# MetalDetector.net
KiCad netlist of a schematic drawn in EAGLE
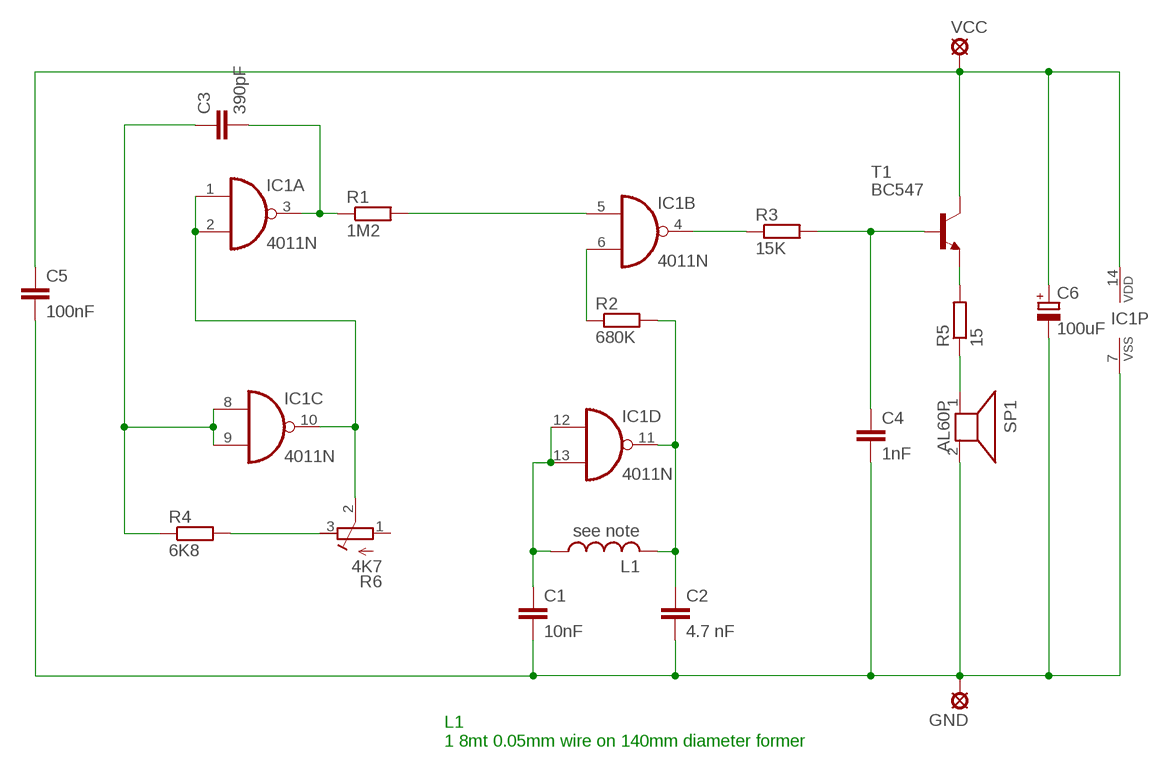
[diagram p0: schematic, sheet 1]

(export (version "E")
  (design (tool "Eeschema 10.0.6"))
  (components
    (comp (ref "C1")
      (value "10nF")
      (footprint "eagle-import:C025-025X050")
      (libsource (lib "eagle-import") (part "C-EU025-025X050"))
    )
    (comp (ref "C2")
      (value "4.7 nF")
      (footprint "eagle-import:C025-025X050")
      (libsource (lib "eagle-import") (part "C-EU025-025X050"))
    )
    (comp (ref "C3")
      (value "390pF")
      (footprint "eagle-import:C025-025X050")
      (libsource (lib "eagle-import") (part "C-EU025-025X050"))
    )
    (comp (ref "C4")
      (value "1nF")
      (footprint "eagle-import:C025-025X050")
      (libsource (lib "eagle-import") (part "C-EU025-025X050"))
    )
    (comp (ref "C5")
      (value "100nF")
      (footprint "eagle-import:C025-025X050")
      (libsource (lib "eagle-import") (part "C-EU025-025X050"))
    )
    (comp (ref "C6")
      (value "100uF")
      (footprint "eagle-import:E5-8,5")
      (libsource (lib "eagle-import") (part "CPOL-EUE5-8.5"))
    )
    (comp (ref "GND")
      (value "LSP10")
      (footprint "eagle-import:LSP10")
      (libsource (lib "eagle-import") (part "LSP10"))
    )
    (comp (ref "IC1")
      (value "4011N")
      (footprint "eagle-import:DIL14")
      (libsource (lib "eagle-import") (part "4011N"))
    )
    (comp (ref "L1")
      (value "see note")
      (footprint "eagle-import:6000-XXXX-RC")
      (libsource (lib "eagle-import") (part "L-US6000-XXX-RC"))
    )
    (comp (ref "R1")
      (value "1M2")
      (footprint "eagle-import:0207_12")
      (libsource (lib "eagle-import") (part "R-EU_0207/12"))
    )
    (comp (ref "R2")
      (value "680K")
      (footprint "eagle-import:0207_12")
      (libsource (lib "eagle-import") (part "R-EU_0207/12"))
    )
    (comp (ref "R3")
      (value "15K")
      (footprint "eagle-import:0207_12")
      (libsource (lib "eagle-import") (part "R-EU_0207/12"))
    )
    (comp (ref "R4")
      (value "6K8")
      (footprint "eagle-import:0207_12")
      (libsource (lib "eagle-import") (part "R-EU_0207/12"))
    )
    (comp (ref "R5")
      (value "15")
      (footprint "eagle-import:0207_12")
      (libsource (lib "eagle-import") (part "R-EU_0207/12"))
    )
    (comp (ref "R6")
      (value "4K7")
      (footprint "eagle-import:RTRIM3339P")
      (libsource (lib "eagle-import") (part "R-TRIMM3339P"))
    )
    (comp (ref "SP1")
      (value "AL60P")
      (footprint "eagle-import:AL60P")
      (libsource (lib "eagle-import") (part "AL60P"))
    )
    (comp (ref "T1")
      (value "BC547")
      (footprint "eagle-import:TO92")
      (libsource (lib "eagle-import") (part "BC547"))
    )
    (comp (ref "VCC")
      (value "LSP10")
      (footprint "eagle-import:LSP10")
      (libsource (lib "eagle-import") (part "LSP10"))
    )
  )
  (nets
    (net (code "1") (name "Net-(IC1A-I0)") (class "Default")
      (node (ref "IC1") (pin "1") (pinfunction "I0_1") (pintype "input"))
      (node (ref "IC1") (pin "10") (pinfunction "O_10") (pintype "output"))
      (node (ref "IC1") (pin "2") (pinfunction "I1_2") (pintype "input"))
      (node (ref "R6") (pin "2") (pinfunction "S_2") (pintype "passive"))
    )
    (net (code "2") (name "Net-(IC1A-O)") (class "Default")
      (node (ref "C3") (pin "2") (pinfunction "2_2") (pintype "passive"))
      (node (ref "IC1") (pin "3") (pinfunction "O_3") (pintype "output"))
      (node (ref "R1") (pin "1") (pinfunction "1_1") (pintype "passive"))
    )
    (net (code "3") (name "Net-(IC1B-I0)") (class "Default")
      (node (ref "IC1") (pin "5") (pinfunction "I0_5") (pintype "input"))
      (node (ref "R1") (pin "2") (pinfunction "2_2") (pintype "passive"))
    )
    (net (code "4") (name "Net-(IC1B-I1)") (class "Default")
      (node (ref "IC1") (pin "6") (pinfunction "I1_6") (pintype "input"))
      (node (ref "R2") (pin "1") (pinfunction "1_1") (pintype "passive"))
    )
    (net (code "5") (name "Net-(IC1B-O)") (class "Default")
      (node (ref "IC1") (pin "4") (pinfunction "O_4") (pintype "output"))
      (node (ref "R3") (pin "1") (pinfunction "1_1") (pintype "passive"))
    )
    (net (code "6") (name "Net-(IC1C-I0)") (class "Default")
      (node (ref "C3") (pin "1") (pinfunction "1_1") (pintype "passive"))
      (node (ref "IC1") (pin "8") (pinfunction "I0_8") (pintype "input"))
      (node (ref "IC1") (pin "9") (pinfunction "I1_9") (pintype "input"))
      (node (ref "R4") (pin "1") (pinfunction "1_1") (pintype "passive"))
    )
    (net (code "7") (name "Net-(IC1D-I0)") (class "Default")
      (node (ref "C1") (pin "1") (pinfunction "1_1") (pintype "passive"))
      (node (ref "IC1") (pin "12") (pinfunction "I0_12") (pintype "input"))
      (node (ref "IC1") (pin "13") (pinfunction "I1_13") (pintype "input"))
      (node (ref "L1") (pin "1") (pinfunction "1_1") (pintype "passive"))
    )
    (net (code "8") (name "Net-(IC1D-O)") (class "Default")
      (node (ref "C2") (pin "1") (pinfunction "1_1") (pintype "passive"))
      (node (ref "IC1") (pin "11") (pinfunction "O_11") (pintype "output"))
      (node (ref "L1") (pin "2") (pinfunction "2_2") (pintype "passive"))
      (node (ref "R2") (pin "2") (pinfunction "2_2") (pintype "passive"))
    )
    (net (code "9") (name "Net-(IC1E-VDD)") (class "Default")
      (node (ref "C5") (pin "1") (pinfunction "1_1") (pintype "passive"))
      (node (ref "C6") (pin "+") (pinfunction "+_+") (pintype "passive"))
      (node (ref "IC1") (pin "14") (pinfunction "VDD_14") (pintype "power_in"))
      (node (ref "T1") (pin "3") (pinfunction "C_3") (pintype "passive"))
      (node (ref "VCC") (pin "MP") (pinfunction "MP_MP") (pintype "passive"))
    )
    (net (code "10") (name "Net-(IC1E-VSS)") (class "Default")
      (node (ref "C1") (pin "2") (pinfunction "2_2") (pintype "passive"))
      (node (ref "C2") (pin "2") (pinfunction "2_2") (pintype "passive"))
      (node (ref "C4") (pin "2") (pinfunction "2_2") (pintype "passive"))
      (node (ref "C5") (pin "2") (pinfunction "2_2") (pintype "passive"))
      (node (ref "C6") (pin "-") (pinfunction "-_-") (pintype "passive"))
      (node (ref "GND") (pin "MP") (pinfunction "MP_MP") (pintype "passive"))
      (node (ref "IC1") (pin "7") (pinfunction "VSS_7") (pintype "power_in"))
      (node (ref "SP1") (pin "2") (pinfunction "2_2") (pintype "passive"))
    )
    (net (code "11") (name "Net-(R5-Pad1)") (class "Default")
      (node (ref "R5") (pin "1") (pinfunction "1_1") (pintype "passive"))
      (node (ref "SP1") (pin "1") (pinfunction "1_1") (pintype "passive"))
    )
    (net (code "12") (name "Net-(R6-E)") (class "Default")
      (node (ref "R4") (pin "2") (pinfunction "2_2") (pintype "passive"))
      (node (ref "R6") (pin "3") (pinfunction "E_3") (pintype "passive"))
    )
    (net (code "13") (name "Net-(T1-B)") (class "Default")
      (node (ref "C4") (pin "1") (pinfunction "1_1") (pintype "passive"))
      (node (ref "R3") (pin "2") (pinfunction "2_2") (pintype "passive"))
      (node (ref "T1") (pin "2") (pinfunction "B_2") (pintype "passive"))
    )
    (net (code "14") (name "Net-(T1-E)") (class "Default")
      (node (ref "R5") (pin "2") (pinfunction "2_2") (pintype "passive"))
      (node (ref "T1") (pin "1") (pinfunction "E_1") (pintype "passive"))
    )
    (net (code "15") (name "unconnected-(R6-A-Pad1)") (class "Default")
      (node (ref "R6") (pin "1") (pinfunction "A_1") (pintype "passive"))
    )
  )
)
